# 10_AD1.net
KiCad netlist of a schematic drawn in Altium Designer
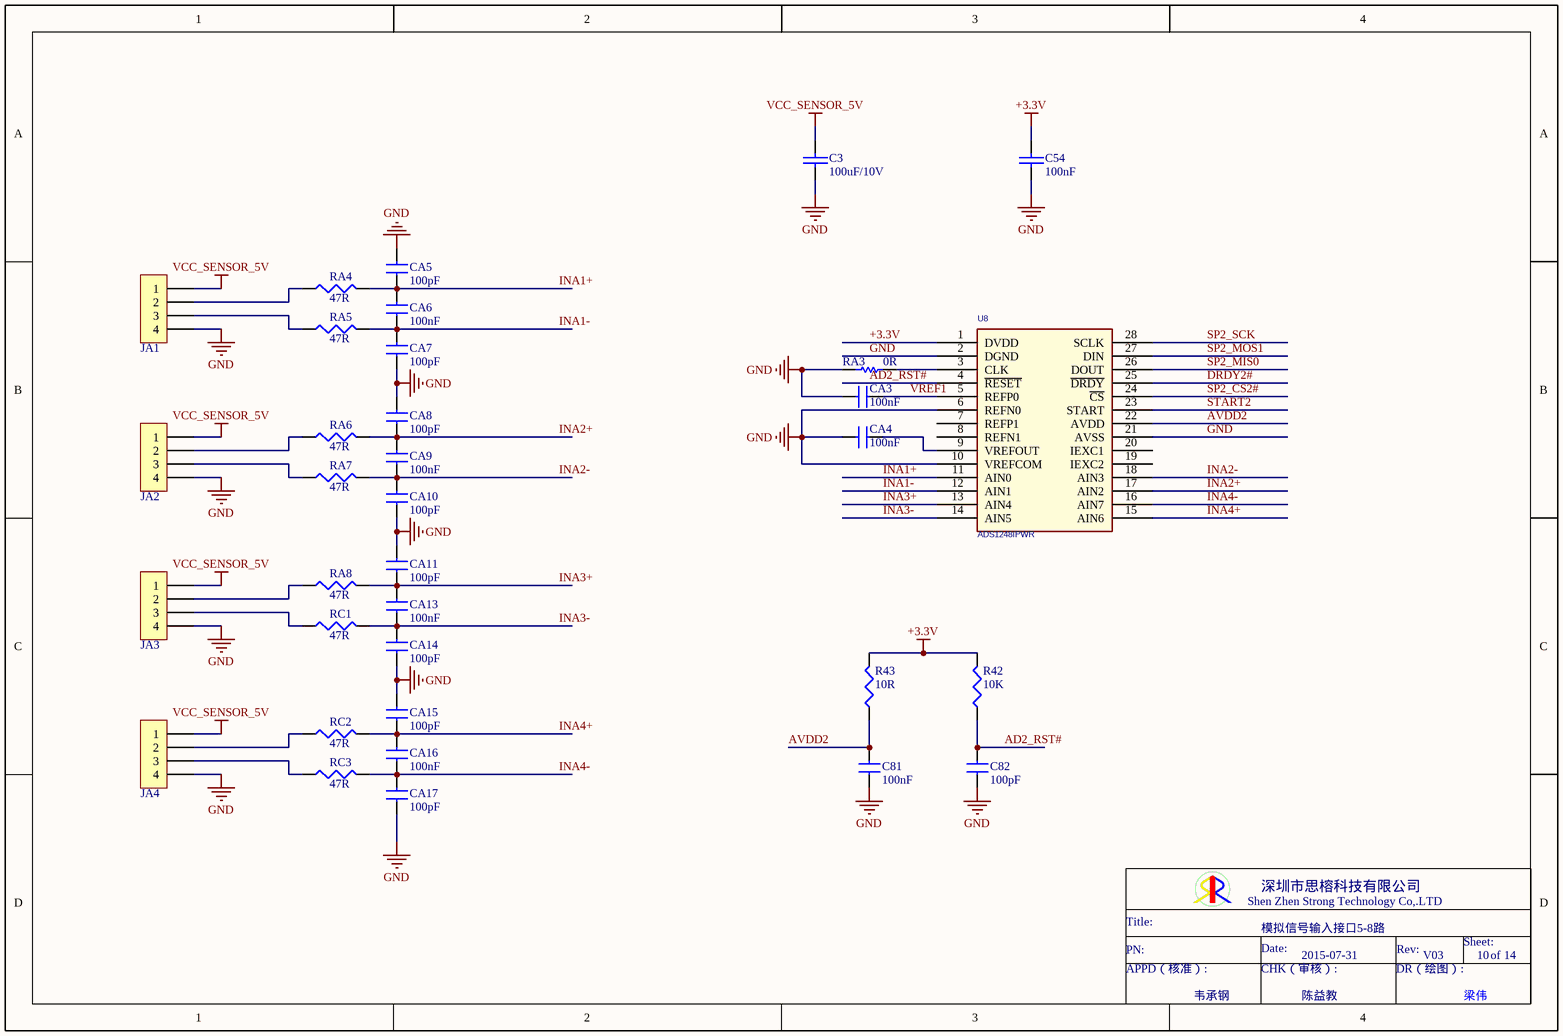
[diagram p0: 10_AD1.SchDoc]

(export (version "E")
  (design (tool "Eeschema 10.0.6"))
  (components
    (comp (ref "C3")
      (value "100uF/10V")
      (footprint "6032")
      (description "Capacitor")
      (libsource (lib "Mylibrary") (part "CAP"))
    )
    (comp (ref "C54")
      (value "100nF")
      (footprint "0603C")
      (description "Capacitor")
      (libsource (lib "Mylibrary") (part "CAP"))
    )
    (comp (ref "C81")
      (value "100nF")
      (footprint "0603C")
      (description "Capacitor")
      (libsource (lib "*") (part "电容"))
    )
    (comp (ref "C82")
      (value "100pF")
      (footprint "0603C")
      (description "Capacitor")
      (libsource (lib "*") (part "电容"))
    )
    (comp (ref "CA3")
      (value "100nF")
      (footprint "0805C")
      (description "Capacitor")
      (libsource (lib "*") (part "电容"))
    )
    (comp (ref "CA4")
      (value "100nF")
      (footprint "0805C")
      (description "Capacitor")
      (libsource (lib "*") (part "电容"))
    )
    (comp (ref "CA5")
      (value "100pF")
      (footprint "0603C")
      (description "Capacitor")
      (libsource (lib "*") (part "电容"))
    )
    (comp (ref "CA6")
      (value "100nF")
      (footprint "0603C")
      (description "Capacitor")
      (libsource (lib "*") (part "电容"))
    )
    (comp (ref "CA7")
      (value "100pF")
      (footprint "0603C")
      (description "Capacitor")
      (libsource (lib "*") (part "电容"))
    )
    (comp (ref "CA8")
      (value "100pF")
      (footprint "0603C")
      (description "Capacitor")
      (libsource (lib "*") (part "电容"))
    )
    (comp (ref "CA9")
      (value "100nF")
      (footprint "0603C")
      (description "Capacitor")
      (libsource (lib "*") (part "电容"))
    )
    (comp (ref "CA10")
      (value "100pF")
      (footprint "0603C")
      (description "Capacitor")
      (libsource (lib "*") (part "电容"))
    )
    (comp (ref "CA11")
      (value "100pF")
      (footprint "0603C")
      (description "Capacitor")
      (libsource (lib "*") (part "电容"))
    )
    (comp (ref "CA13")
      (value "100nF")
      (footprint "0603C")
      (description "Capacitor")
      (libsource (lib "*") (part "电容"))
    )
    (comp (ref "CA14")
      (value "100pF")
      (footprint "0603C")
      (description "Capacitor")
      (libsource (lib "*") (part "电容"))
    )
    (comp (ref "CA15")
      (value "100pF")
      (footprint "0603C")
      (description "Capacitor")
      (libsource (lib "*") (part "电容"))
    )
    (comp (ref "CA16")
      (value "100nF")
      (footprint "0603C")
      (description "Capacitor")
      (libsource (lib "*") (part "电容"))
    )
    (comp (ref "CA17")
      (value "100pF")
      (footprint "0603C")
      (description "Capacitor")
      (libsource (lib "*") (part "电容"))
    )
    (comp (ref "JA1") (value "XH-4A") (footprint "CN4-2.54") (libsource (lib "Mylibrary") (part "CON4")))
    (comp (ref "JA2") (value "XH-4A") (footprint "CN4-2.54") (libsource (lib "Mylibrary") (part "CON4")))
    (comp (ref "JA3") (value "XH-4A") (footprint "CN4-2.54") (libsource (lib "Mylibrary") (part "CON4")))
    (comp (ref "JA4") (value "XH-4A") (footprint "CN4-2.54") (libsource (lib "Mylibrary") (part "CON4")))
    (comp (ref "R42") (value "10K") (footprint "0603R") (libsource (lib "*") (part "RES1")))
    (comp (ref "R43") (value "10R") (footprint "0603R") (libsource (lib "*") (part "RES1")))
    (comp (ref "RA3") (value "0R") (footprint "0603R") (libsource (lib "Mylibrary") (part "RES")))
    (comp (ref "RA4") (value "47R") (footprint "0603R") (libsource (lib "*") (part "RES1")))
    (comp (ref "RA5") (value "47R") (footprint "0603R") (libsource (lib "*") (part "RES1")))
    (comp (ref "RA6") (value "47R") (footprint "0603R") (libsource (lib "*") (part "RES1")))
    (comp (ref "RA7") (value "47R") (footprint "0603R") (libsource (lib "*") (part "RES1")))
    (comp (ref "RA8") (value "47R") (footprint "0603R") (libsource (lib "*") (part "RES1")))
    (comp (ref "RC1") (value "47R") (footprint "0603R") (libsource (lib "*") (part "RES1")))
    (comp (ref "RC2") (value "47R") (footprint "0603R") (libsource (lib "*") (part "RES1")))
    (comp (ref "RC3") (value "47R") (footprint "0603R") (libsource (lib "*") (part "RES1")))
    (comp (ref "U8")
      (value "ADS1248IPWR")
      (footprint "SOIC28")
      (description "IC - 10 BIT FET BUS SWITCH")
      (fields (field (name "MANUFACTURER") "Texas Instruments"))
      (libsource (lib "Mylibrary") (part "ADS1248IPWR"))
    )
  )
  (nets
    (net (code "1") (name "+3.3V") (class "Default")
      (node (ref "C54") (pin "1") (pinfunction "1_1") (pintype "passive"))
      (node (ref "R42") (pin "2") (pinfunction "2_2") (pintype "passive"))
      (node (ref "R43") (pin "2") (pinfunction "2_2") (pintype "passive"))
      (node (ref "U8") (pin "1") (pinfunction "DVDD_1") (pintype "passive"))
    )
    (net (code "2") (name "/AD2_RST#") (class "Default")
      (node (ref "C82") (pin "1") (pinfunction "1_1") (pintype "passive"))
      (node (ref "R42") (pin "1") (pinfunction "1_1") (pintype "passive"))
      (node (ref "U8") (pin "4") (pinfunction "~{RESET}_4") (pintype "passive"))
    )
    (net (code "3") (name "/AVDD2") (class "Default")
      (node (ref "C81") (pin "1") (pinfunction "1_1") (pintype "passive"))
      (node (ref "R43") (pin "1") (pinfunction "1_1") (pintype "passive"))
      (node (ref "U8") (pin "22") (pinfunction "AVDD_22") (pintype "passive"))
    )
    (net (code "4") (name "/DRDY2#") (class "Default")
      (node (ref "U8") (pin "25") (pinfunction "~{DRDY}_25") (pintype "passive"))
    )
    (net (code "5") (name "/INA1+") (class "Default")
      (node (ref "CA5") (pin "2") (pinfunction "2_2") (pintype "passive"))
      (node (ref "CA6") (pin "1") (pinfunction "1_1") (pintype "passive"))
      (node (ref "RA4") (pin "2") (pinfunction "2_2") (pintype "passive"))
      (node (ref "U8") (pin "11") (pinfunction "AIN0_11") (pintype "passive"))
    )
    (net (code "6") (name "/INA1-") (class "Default")
      (node (ref "CA6") (pin "2") (pinfunction "2_2") (pintype "passive"))
      (node (ref "CA7") (pin "1") (pinfunction "1_1") (pintype "passive"))
      (node (ref "RA5") (pin "2") (pinfunction "2_2") (pintype "passive"))
      (node (ref "U8") (pin "12") (pinfunction "AIN1_12") (pintype "power_in"))
    )
    (net (code "7") (name "/INA2+") (class "Default")
      (node (ref "CA8") (pin "2") (pinfunction "2_2") (pintype "passive"))
      (node (ref "CA9") (pin "1") (pinfunction "1_1") (pintype "passive"))
      (node (ref "RA6") (pin "2") (pinfunction "2_2") (pintype "passive"))
      (node (ref "U8") (pin "17") (pinfunction "AIN2_17") (pintype "passive"))
    )
    (net (code "8") (name "/INA2-") (class "Default")
      (node (ref "CA10") (pin "1") (pinfunction "1_1") (pintype "passive"))
      (node (ref "CA9") (pin "2") (pinfunction "2_2") (pintype "passive"))
      (node (ref "RA7") (pin "2") (pinfunction "2_2") (pintype "passive"))
      (node (ref "U8") (pin "18") (pinfunction "AIN3_18") (pintype "passive"))
    )
    (net (code "9") (name "/INA3+") (class "Default")
      (node (ref "CA11") (pin "2") (pinfunction "2_2") (pintype "passive"))
      (node (ref "CA13") (pin "1") (pinfunction "1_1") (pintype "passive"))
      (node (ref "RA8") (pin "2") (pinfunction "2_2") (pintype "passive"))
      (node (ref "U8") (pin "13") (pinfunction "AIN4_13") (pintype "passive"))
    )
    (net (code "10") (name "/INA3-") (class "Default")
      (node (ref "CA13") (pin "2") (pinfunction "2_2") (pintype "passive"))
      (node (ref "CA14") (pin "1") (pinfunction "1_1") (pintype "passive"))
      (node (ref "RC1") (pin "2") (pinfunction "2_2") (pintype "passive"))
      (node (ref "U8") (pin "14") (pinfunction "AIN5_14") (pintype "passive"))
    )
    (net (code "11") (name "/INA4+") (class "Default")
      (node (ref "CA15") (pin "2") (pinfunction "2_2") (pintype "passive"))
      (node (ref "CA16") (pin "1") (pinfunction "1_1") (pintype "passive"))
      (node (ref "RC2") (pin "2") (pinfunction "2_2") (pintype "passive"))
      (node (ref "U8") (pin "15") (pinfunction "AIN6_15") (pintype "passive"))
    )
    (net (code "12") (name "/INA4-") (class "Default")
      (node (ref "CA16") (pin "2") (pinfunction "2_2") (pintype "passive"))
      (node (ref "CA17") (pin "1") (pinfunction "1_1") (pintype "passive"))
      (node (ref "RC3") (pin "2") (pinfunction "2_2") (pintype "passive"))
      (node (ref "U8") (pin "16") (pinfunction "AIN7_16") (pintype "passive"))
    )
    (net (code "13") (name "/SP2_CS2#") (class "Default")
      (node (ref "U8") (pin "24") (pinfunction "~{CS}_24") (pintype "power_in"))
    )
    (net (code "14") (name "/SP2_MIS0") (class "Default")
      (node (ref "U8") (pin "26") (pinfunction "DOUT_26") (pintype "passive"))
    )
    (net (code "15") (name "/SP2_MOS1") (class "Default")
      (node (ref "U8") (pin "27") (pinfunction "DIN_27") (pintype "passive"))
    )
    (net (code "16") (name "/SP2_SCK") (class "Default")
      (node (ref "U8") (pin "28") (pinfunction "SCLK_28") (pintype "passive"))
    )
    (net (code "17") (name "/START2") (class "Default")
      (node (ref "U8") (pin "23") (pinfunction "START_23") (pintype "passive"))
    )
    (net (code "18") (name "/VREF1") (class "Default")
      (node (ref "CA3") (pin "1") (pinfunction "1_1") (pintype "passive"))
      (node (ref "U8") (pin "5") (pinfunction "REFP0_5") (pintype "passive"))
    )
    (net (code "19") (name "GND") (class "Default")
      (node (ref "C3") (pin "2") (pinfunction "2_2") (pintype "passive"))
      (node (ref "C54") (pin "2") (pinfunction "2_2") (pintype "passive"))
      (node (ref "C81") (pin "2") (pinfunction "2_2") (pintype "passive"))
      (node (ref "C82") (pin "2") (pinfunction "2_2") (pintype "passive"))
      (node (ref "CA10") (pin "2") (pinfunction "2_2") (pintype "passive"))
      (node (ref "CA11") (pin "1") (pinfunction "1_1") (pintype "passive"))
      (node (ref "CA14") (pin "2") (pinfunction "2_2") (pintype "passive"))
      (node (ref "CA15") (pin "1") (pinfunction "1_1") (pintype "passive"))
      (node (ref "CA17") (pin "2") (pinfunction "2_2") (pintype "passive"))
      (node (ref "CA3") (pin "2") (pinfunction "2_2") (pintype "passive"))
      (node (ref "CA4") (pin "2") (pinfunction "2_2") (pintype "passive"))
      (node (ref "CA5") (pin "1") (pinfunction "1_1") (pintype "passive"))
      (node (ref "CA7") (pin "2") (pinfunction "2_2") (pintype "passive"))
      (node (ref "CA8") (pin "1") (pinfunction "1_1") (pintype "passive"))
      (node (ref "JA1") (pin "4") (pinfunction "4_4") (pintype "passive"))
      (node (ref "JA2") (pin "4") (pinfunction "4_4") (pintype "passive"))
      (node (ref "JA3") (pin "4") (pinfunction "4_4") (pintype "passive"))
      (node (ref "JA4") (pin "4") (pinfunction "4_4") (pintype "passive"))
      (node (ref "RA3") (pin "1") (pinfunction "1_1") (pintype "passive"))
      (node (ref "U8") (pin "10") (pinfunction "VREFCOM_10") (pintype "passive"))
      (node (ref "U8") (pin "2") (pinfunction "DGND_2") (pintype "passive"))
      (node (ref "U8") (pin "21") (pinfunction "AVSS_21") (pintype "passive"))
      (node (ref "U8") (pin "6") (pinfunction "REFN0_6") (pintype "passive"))
    )
    (net (code "20") (name "Net-(JA1-Pad2)") (class "Default")
      (node (ref "JA1") (pin "2") (pinfunction "2_2") (pintype "passive"))
      (node (ref "RA4") (pin "1") (pinfunction "1_1") (pintype "passive"))
    )
    (net (code "21") (name "Net-(JA1-Pad3)") (class "Default")
      (node (ref "JA1") (pin "3") (pinfunction "3_3") (pintype "passive"))
      (node (ref "RA5") (pin "1") (pinfunction "1_1") (pintype "passive"))
    )
    (net (code "22") (name "Net-(JA2-Pad2)") (class "Default")
      (node (ref "JA2") (pin "2") (pinfunction "2_2") (pintype "passive"))
      (node (ref "RA6") (pin "1") (pinfunction "1_1") (pintype "passive"))
    )
    (net (code "23") (name "Net-(JA2-Pad3)") (class "Default")
      (node (ref "JA2") (pin "3") (pinfunction "3_3") (pintype "passive"))
      (node (ref "RA7") (pin "1") (pinfunction "1_1") (pintype "passive"))
    )
    (net (code "24") (name "Net-(JA3-Pad2)") (class "Default")
      (node (ref "JA3") (pin "2") (pinfunction "2_2") (pintype "passive"))
      (node (ref "RA8") (pin "1") (pinfunction "1_1") (pintype "passive"))
    )
    (net (code "25") (name "Net-(JA3-Pad3)") (class "Default")
      (node (ref "JA3") (pin "3") (pinfunction "3_3") (pintype "passive"))
      (node (ref "RC1") (pin "1") (pinfunction "1_1") (pintype "passive"))
    )
    (net (code "26") (name "Net-(JA4-Pad2)") (class "Default")
      (node (ref "JA4") (pin "2") (pinfunction "2_2") (pintype "passive"))
      (node (ref "RC2") (pin "1") (pinfunction "1_1") (pintype "passive"))
    )
    (net (code "27") (name "Net-(JA4-Pad3)") (class "Default")
      (node (ref "JA4") (pin "3") (pinfunction "3_3") (pintype "passive"))
      (node (ref "RC3") (pin "1") (pinfunction "1_1") (pintype "passive"))
    )
    (net (code "28") (name "Net-(U8-CLK)") (class "Default")
      (node (ref "RA3") (pin "2") (pinfunction "2_2") (pintype "passive"))
      (node (ref "U8") (pin "3") (pinfunction "CLK_3") (pintype "passive"))
    )
    (net (code "29") (name "Net-(U8-VREFOUT)") (class "Default")
      (node (ref "CA4") (pin "1") (pinfunction "1_1") (pintype "passive"))
      (node (ref "U8") (pin "9") (pinfunction "VREFOUT_9") (pintype "passive"))
    )
    (net (code "30") (name "VCC_SENSOR_5V") (class "Default")
      (node (ref "C3") (pin "1") (pinfunction "1_1") (pintype "passive"))
      (node (ref "JA1") (pin "1") (pinfunction "1_1") (pintype "passive"))
      (node (ref "JA2") (pin "1") (pinfunction "1_1") (pintype "passive"))
      (node (ref "JA3") (pin "1") (pinfunction "1_1") (pintype "passive"))
      (node (ref "JA4") (pin "1") (pinfunction "1_1") (pintype "passive"))
    )
    (net (code "31") (name "unconnected-(U8-IEXC1-Pad20)") (class "Default")
      (node (ref "U8") (pin "20") (pinfunction "IEXC1_20") (pintype "passive"))
    )
    (net (code "32") (name "unconnected-(U8-IEXC2-Pad19)") (class "Default")
      (node (ref "U8") (pin "19") (pinfunction "IEXC2_19") (pintype "passive"))
    )
    (net (code "33") (name "unconnected-(U8-REFN1-Pad8)") (class "Default")
      (node (ref "U8") (pin "8") (pinfunction "REFN1_8") (pintype "passive"))
    )
    (net (code "34") (name "unconnected-(U8-REFP1-Pad7)") (class "Default")
      (node (ref "U8") (pin "7") (pinfunction "REFP1_7") (pintype "passive"))
    )
  )
)
